# Recepitor.net
KiCad netlist of a schematic drawn in Altium Designer
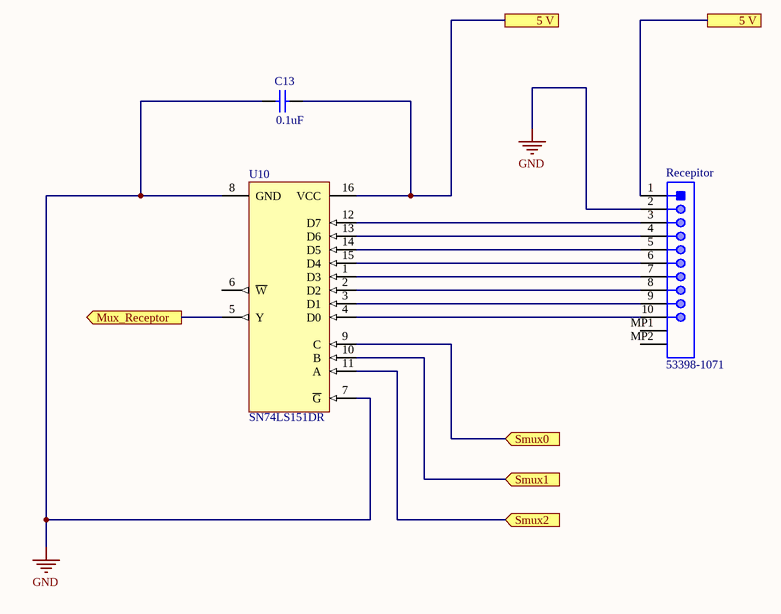
[diagram p0: Recepitor.SchDoc]

(export (version "E")
  (design (tool "Eeschema 10.0.6"))
  (components
    (comp (ref "C13")
      (value "710-885012206071")
      (footprint "CAPC1608X90X30LL10T20")
      (fields
        (field (name "VOLTAGE") "25Vdc")
        (field (name "MANUFACTURER") "SamsungElectro-Mechanics")
        (field (name "CAPACITANCE VALUE") "0.1uF")
        (field (name "TOLERANCE") "10%")
      )
      (libsource (lib "CAP 0603 100nF") (part "CMP-2000-06092-1"))
    )
    (comp (ref "Recepitor")
      (value "53398-1071")
      (footprint "MOLX-53398-1071_V")
      (description "Male Header, Pitch 1.25 mm, 1 x 10 Position, Height 4.7 mm, -40 to 85 degC, RoHS, Tape and Reel")
      (fields (field (name "MANUFACTURER") "Molex"))
      (libsource (lib "Molex_53398-1071") (part "CMP-2000-05635-1"))
    )
    (comp (ref "U10")
      (value "SN74LS151DR")
      (footprint "D0016A_L")
      (description "8-Line To 1-Line Data Selectors/Multiplexers, D0016A, LARGE T&R")
      (fields
        (field (name "MANUFACTURER") "Texas Instruments")
        (field (name "GENERIC PART NUMBER") "SN74LS151")
      )
      (libsource (lib "mux SN74LS151DR") (part "CMP-1633-00148-1"))
    )
  )
  (nets
    (net (code "1") (name "/5 V") (class "Default")
      (node (ref "C13") (pin "2") (pinfunction "2_2") (pintype "passive"))
      (node (ref "Recepitor") (pin "1") (pinfunction "1_1") (pintype "passive"))
      (node (ref "U10") (pin "16") (pinfunction "VCC_16") (pintype "power_in"))
    )
    (net (code "2") (name "/Mux_Receptor") (class "Default")
      (node (ref "U10") (pin "5") (pinfunction "Y_5") (pintype "output"))
    )
    (net (code "3") (name "/Smux0") (class "Default")
      (node (ref "U10") (pin "9") (pinfunction "C_9") (pintype "input"))
    )
    (net (code "4") (name "/Smux1") (class "Default")
      (node (ref "U10") (pin "10") (pinfunction "B_10") (pintype "input"))
    )
    (net (code "5") (name "/Smux2") (class "Default")
      (node (ref "U10") (pin "11") (pinfunction "A_11") (pintype "input"))
    )
    (net (code "6") (name "GND") (class "Default")
      (node (ref "C13") (pin "1") (pinfunction "1_1") (pintype "passive"))
      (node (ref "Recepitor") (pin "2") (pinfunction "2_2") (pintype "passive"))
      (node (ref "U10") (pin "7") (pinfunction "~{G}_7") (pintype "input"))
      (node (ref "U10") (pin "8") (pinfunction "GND_8") (pintype "power_in"))
    )
    (net (code "7") (name "Net-(U10-D0)") (class "Default")
      (node (ref "Recepitor") (pin "10") (pinfunction "10_10") (pintype "passive"))
      (node (ref "U10") (pin "4") (pinfunction "D0_4") (pintype "input"))
    )
    (net (code "8") (name "Net-(U10-D1)") (class "Default")
      (node (ref "Recepitor") (pin "9") (pinfunction "9_9") (pintype "passive"))
      (node (ref "U10") (pin "3") (pinfunction "D1_3") (pintype "input"))
    )
    (net (code "9") (name "Net-(U10-D2)") (class "Default")
      (node (ref "Recepitor") (pin "8") (pinfunction "8_8") (pintype "passive"))
      (node (ref "U10") (pin "2") (pinfunction "D2_2") (pintype "input"))
    )
    (net (code "10") (name "Net-(U10-D3)") (class "Default")
      (node (ref "Recepitor") (pin "7") (pinfunction "7_7") (pintype "passive"))
      (node (ref "U10") (pin "1") (pinfunction "D3_1") (pintype "input"))
    )
    (net (code "11") (name "Net-(U10-D4)") (class "Default")
      (node (ref "Recepitor") (pin "6") (pinfunction "6_6") (pintype "passive"))
      (node (ref "U10") (pin "15") (pinfunction "D4_15") (pintype "input"))
    )
    (net (code "12") (name "Net-(U10-D5)") (class "Default")
      (node (ref "Recepitor") (pin "5") (pinfunction "5_5") (pintype "passive"))
      (node (ref "U10") (pin "14") (pinfunction "D5_14") (pintype "input"))
    )
    (net (code "13") (name "Net-(U10-D6)") (class "Default")
      (node (ref "Recepitor") (pin "4") (pinfunction "4_4") (pintype "passive"))
      (node (ref "U10") (pin "13") (pinfunction "D6_13") (pintype "input"))
    )
    (net (code "14") (name "Net-(U10-D7)") (class "Default")
      (node (ref "Recepitor") (pin "3") (pinfunction "3_3") (pintype "passive"))
      (node (ref "U10") (pin "12") (pinfunction "D7_12") (pintype "input"))
    )
    (net (code "15") (name "unconnected-(Recepitor-PadMP1)") (class "Default")
      (node (ref "Recepitor") (pin "MP1") (pinfunction "MP1_MP1") (pintype "passive"))
    )
    (net (code "16") (name "unconnected-(Recepitor-PadMP2)") (class "Default")
      (node (ref "Recepitor") (pin "MP2") (pinfunction "MP2_MP2") (pintype "passive"))
    )
    (net (code "17") (name "unconnected-(U10-~{W}-Pad6)") (class "Default")
      (node (ref "U10") (pin "6") (pinfunction "~{W}_6") (pintype "output"))
    )
  )
)
